# PROC099A_LP_Connector.net
KiCad netlist of a schematic drawn in Altium Designer
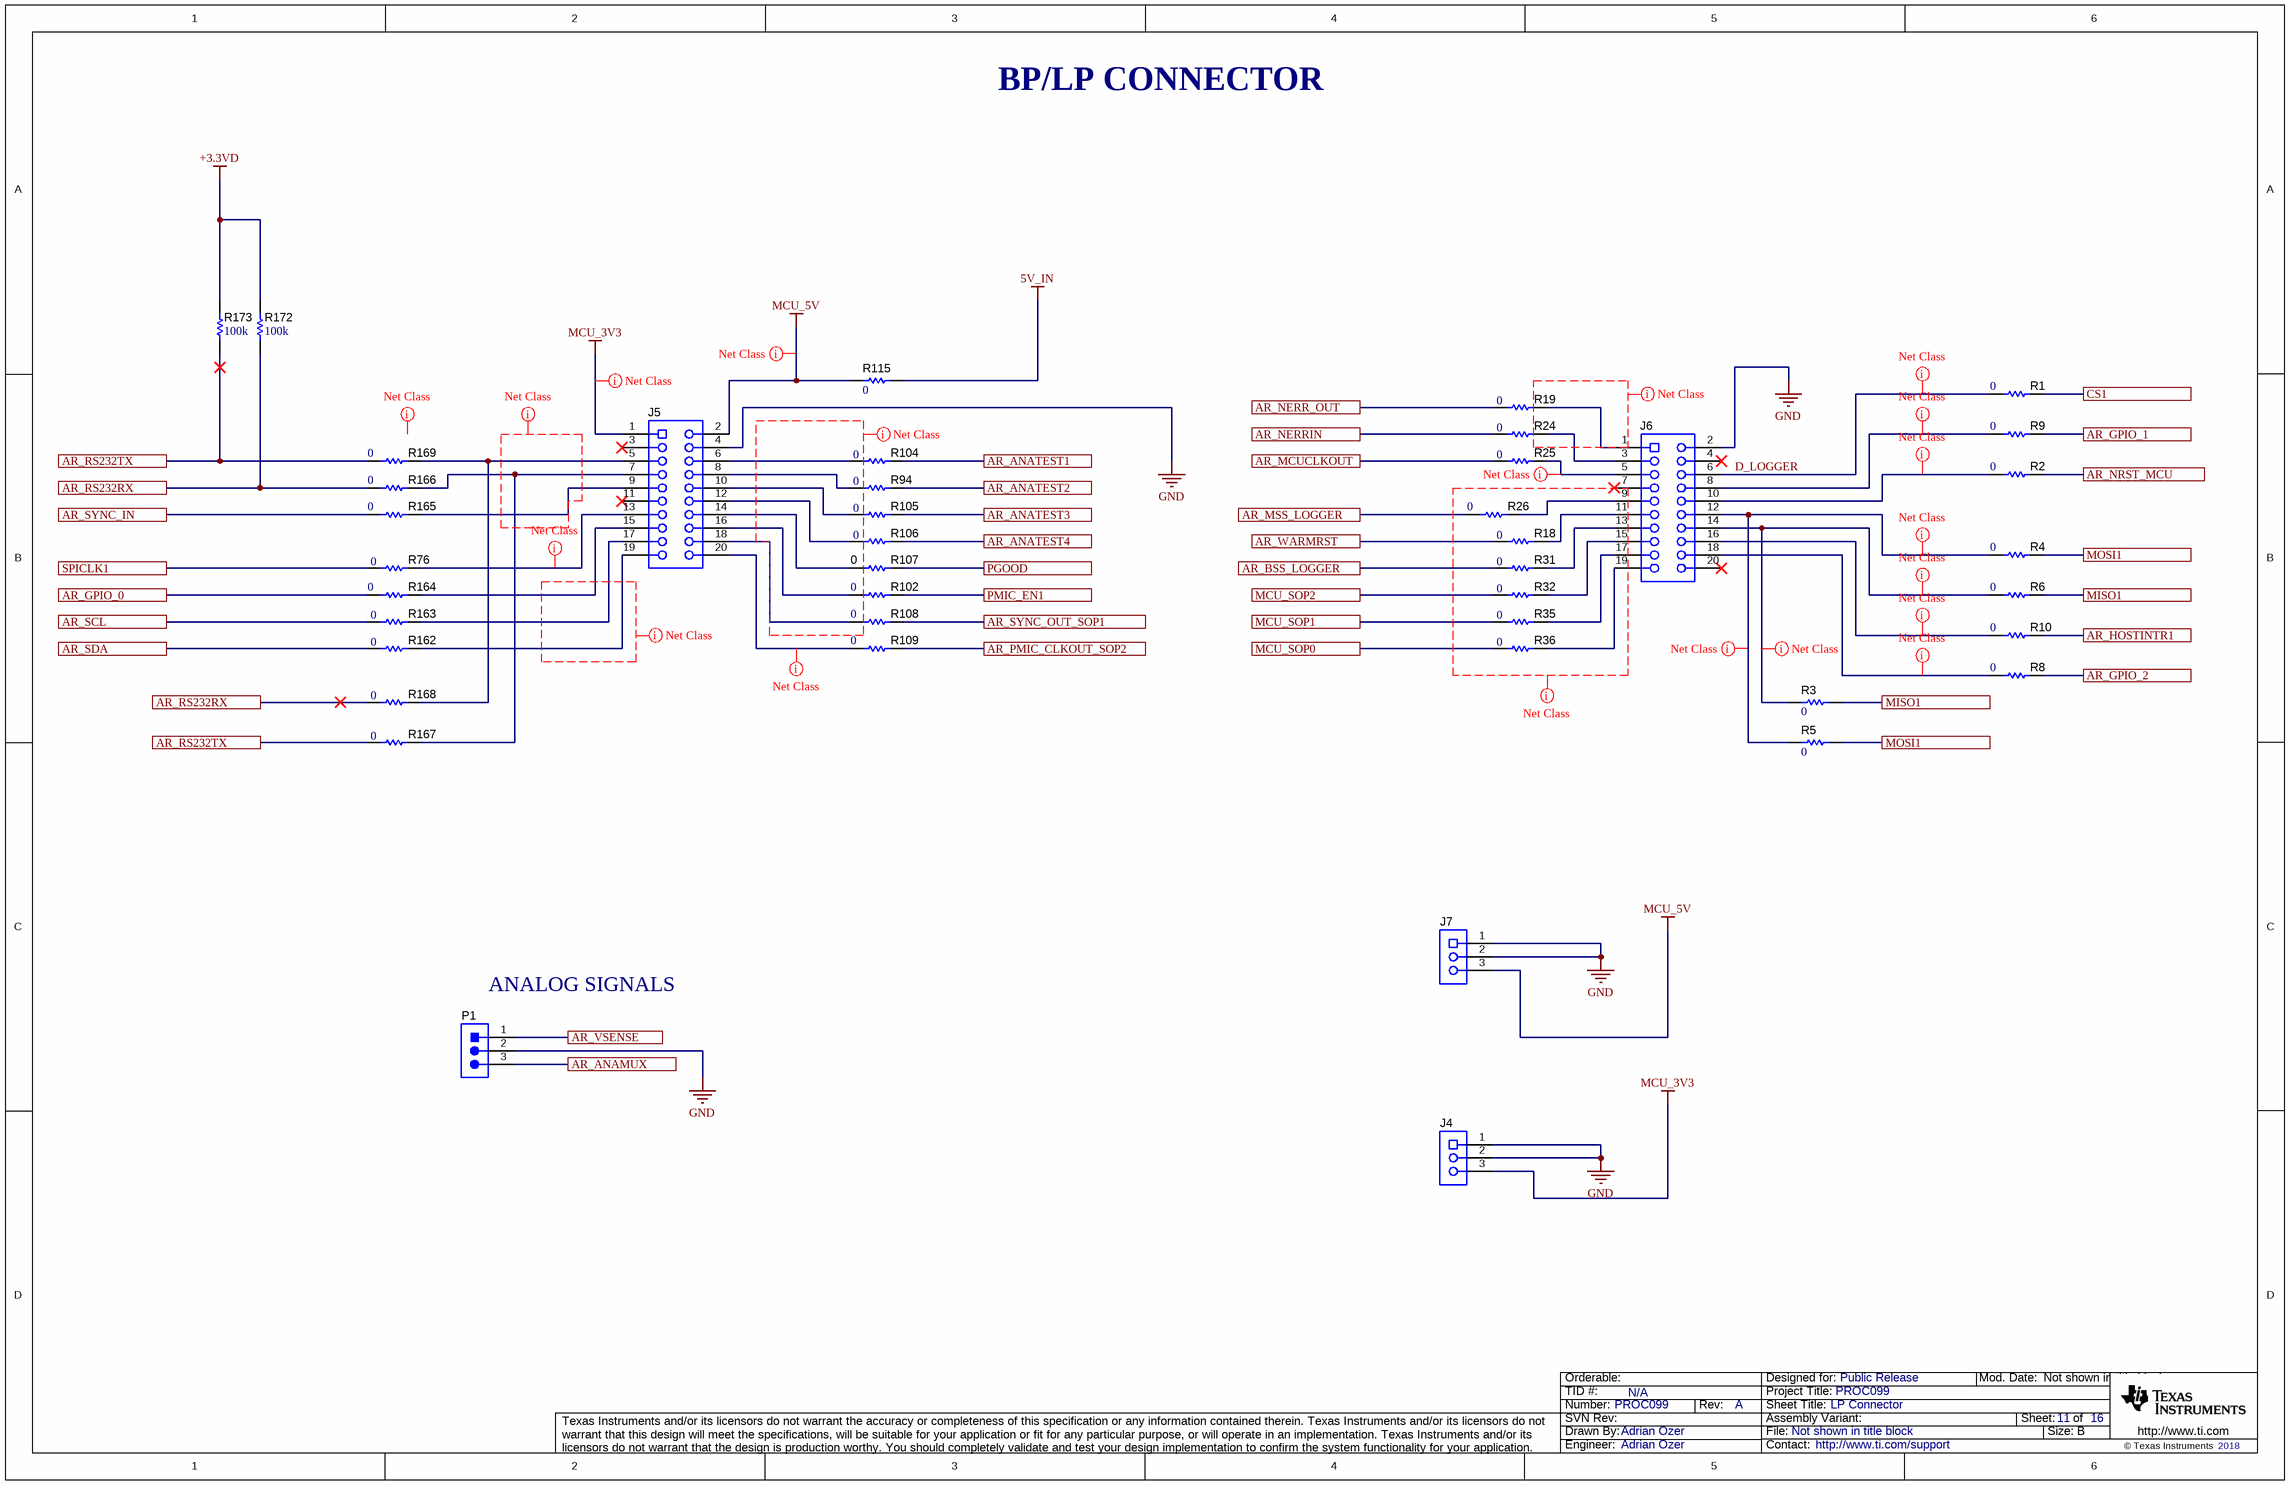
[diagram p0: PROC099A_LP Connector.SchDoc]

(export (version "E")
  (design (tool "Eeschema 10.0.6"))
  (components
    (comp (ref "J4")
      (value "SSM-103-S-SV")
      (footprint "Samtec_SSM-103-x-SV")
      (description "Receptacle, 2.54mm, 3x1, Gold with Tin tail, SMT")
      (fields (field (name "MANUFACTURER") "Samtec"))
      (libsource (lib "Altium Vault - TI") (part "CMP-0078183-1"))
    )
    (comp (ref "J5")
      (value "SSM-110-S-DV")
      (footprint "Samtec_SSM-110-x-DV")
      (description "Receptacle, 2.54mm, 10x2, Gold with Tin tail, SMT")
      (fields (field (name "MANUFACTURER") "Samtec"))
      (libsource (lib "Altium Vault - TI") (part "CMP-0078182-1"))
    )
    (comp (ref "J6")
      (value "SSM-110-S-DV")
      (footprint "Samtec_SSM-110-x-DV")
      (description "Receptacle, 2.54mm, 10x2, Gold with Tin tail, SMT")
      (fields (field (name "MANUFACTURER") "Samtec"))
      (libsource (lib "Altium Vault - TI") (part "CMP-0078182-1"))
    )
    (comp (ref "J7")
      (value "SSM-103-S-SV")
      (footprint "Samtec_SSM-103-x-SV")
      (description "Receptacle, 2.54mm, 3x1, Gold with Tin tail, SMT")
      (fields (field (name "MANUFACTURER") "Samtec"))
      (libsource (lib "Altium Vault - TI") (part "CMP-0078183-1"))
    )
    (comp (ref "P1")
      (value "TSW-103-07-T-S")
      (footprint "Samtec_TSW-103-07-T-S")
      (description "Header, 2.54 mm, 3x1, Tin, TH")
      (fields (field (name "MANUFACTURER") "Samtec"))
      (libsource (lib "Altium Vault - TI") (part "Header_3x1"))
    )
    (comp (ref "R1")
      (value "CRCW02010000Z0ED")
      (footprint "0201_Silk")
      (description "RES, 0, 5%, 0.05 W, 0201")
      (fields (field (name "MANUFACTURER") "Vishay-Dale") (field (name "VALUEDISPLAYED") "0"))
      (libsource (lib "Altium Vault - TI") (part "Resistor"))
    )
    (comp (ref "R2")
      (value "CRCW02010000Z0ED")
      (footprint "0201_Silk")
      (description "RES, 0, 5%, 0.05 W, 0201")
      (fields (field (name "MANUFACTURER") "Vishay-Dale") (field (name "VALUEDISPLAYED") "0"))
      (libsource (lib "Altium Vault - TI") (part "Resistor"))
    )
    (comp (ref "R3")
      (value "CRCW02010000Z0ED")
      (footprint "0201_Silk")
      (description "RES, 0, 5%, 0.05 W, 0201")
      (fields (field (name "MANUFACTURER") "Vishay-Dale") (field (name "VALUEDISPLAYED") "0"))
      (libsource (lib "Altium Vault - TI") (part "Resistor"))
    )
    (comp (ref "R4")
      (value "CRCW02010000Z0ED")
      (footprint "0201_Silk")
      (description "RES, 0, 5%, 0.05 W, 0201")
      (fields (field (name "MANUFACTURER") "Vishay-Dale") (field (name "VALUEDISPLAYED") "0"))
      (libsource (lib "Altium Vault - TI") (part "Resistor"))
    )
    (comp (ref "R5")
      (value "CRCW02010000Z0ED")
      (footprint "0201_Silk")
      (description "RES, 0, 5%, 0.05 W, 0201")
      (fields (field (name "MANUFACTURER") "Vishay-Dale") (field (name "VALUEDISPLAYED") "0"))
      (libsource (lib "Altium Vault - TI") (part "Resistor"))
    )
    (comp (ref "R6")
      (value "CRCW02010000Z0ED")
      (footprint "0201_Silk")
      (description "RES, 0, 5%, 0.05 W, 0201")
      (fields (field (name "MANUFACTURER") "Vishay-Dale") (field (name "VALUEDISPLAYED") "0"))
      (libsource (lib "Altium Vault - TI") (part "Resistor"))
    )
    (comp (ref "R8")
      (value "CRCW02010000Z0ED")
      (footprint "0201_Silk")
      (description "RES, 0, 5%, 0.05 W, 0201")
      (fields (field (name "MANUFACTURER") "Vishay-Dale") (field (name "VALUEDISPLAYED") "0"))
      (libsource (lib "Altium Vault - TI") (part "Resistor"))
    )
    (comp (ref "R9")
      (value "CRCW02010000Z0ED")
      (footprint "0201_Silk")
      (description "RES, 0, 5%, 0.05 W, 0201")
      (fields (field (name "MANUFACTURER") "Vishay-Dale") (field (name "VALUEDISPLAYED") "0"))
      (libsource (lib "Altium Vault - TI") (part "Resistor"))
    )
    (comp (ref "R10")
      (value "CRCW02010000Z0ED")
      (footprint "0201_Silk")
      (description "RES, 0, 5%, 0.05 W, 0201")
      (fields (field (name "MANUFACTURER") "Vishay-Dale") (field (name "VALUEDISPLAYED") "0"))
      (libsource (lib "Altium Vault - TI") (part "Resistor"))
    )
    (comp (ref "R18")
      (value "CRCW02010000Z0ED")
      (footprint "0201_Silk")
      (description "RES, 0, 5%, 0.05 W, 0201")
      (fields (field (name "MANUFACTURER") "Vishay-Dale") (field (name "VALUEDISPLAYED") "0"))
      (libsource (lib "Altium Vault - TI") (part "Resistor"))
    )
    (comp (ref "R19")
      (value "CRCW02010000Z0ED")
      (footprint "0201_Silk")
      (description "RES, 0, 5%, 0.05 W, 0201")
      (fields (field (name "MANUFACTURER") "Vishay-Dale") (field (name "VALUEDISPLAYED") "0"))
      (libsource (lib "Altium Vault - TI") (part "Resistor"))
    )
    (comp (ref "R24")
      (value "CRCW02010000Z0ED")
      (footprint "0201_Silk")
      (description "RES, 0, 5%, 0.05 W, 0201")
      (fields (field (name "MANUFACTURER") "Vishay-Dale") (field (name "VALUEDISPLAYED") "0"))
      (libsource (lib "Altium Vault - TI") (part "Resistor"))
    )
    (comp (ref "R25")
      (value "CRCW02010000Z0ED")
      (footprint "0201_Silk")
      (description "RES, 0, 5%, 0.05 W, 0201")
      (fields (field (name "MANUFACTURER") "Vishay-Dale") (field (name "VALUEDISPLAYED") "0"))
      (libsource (lib "Altium Vault - TI") (part "Resistor"))
    )
    (comp (ref "R26")
      (value "CRCW02010000Z0ED")
      (footprint "0201_Silk")
      (description "RES, 0, 5%, 0.05 W, 0201")
      (fields (field (name "MANUFACTURER") "Vishay-Dale") (field (name "VALUEDISPLAYED") "0"))
      (libsource (lib "Altium Vault - TI") (part "Resistor"))
    )
    (comp (ref "R31")
      (value "CRCW02010000Z0ED")
      (footprint "0201_Silk")
      (description "RES, 0, 5%, 0.05 W, 0201")
      (fields (field (name "MANUFACTURER") "Vishay-Dale") (field (name "VALUEDISPLAYED") "0"))
      (libsource (lib "Altium Vault - TI") (part "Resistor"))
    )
    (comp (ref "R32")
      (value "CRCW02010000Z0ED")
      (footprint "0201_Silk")
      (description "RES, 0, 5%, 0.05 W, 0201")
      (fields (field (name "MANUFACTURER") "Vishay-Dale") (field (name "VALUEDISPLAYED") "0"))
      (libsource (lib "Altium Vault - TI") (part "Resistor"))
    )
    (comp (ref "R35")
      (value "CRCW02010000Z0ED")
      (footprint "0201_Silk")
      (description "RES, 0, 5%, 0.05 W, 0201")
      (fields (field (name "MANUFACTURER") "Vishay-Dale") (field (name "VALUEDISPLAYED") "0"))
      (libsource (lib "Altium Vault - TI") (part "Resistor"))
    )
    (comp (ref "R36")
      (value "CRCW02010000Z0ED")
      (footprint "0201_Silk")
      (description "RES, 0, 5%, 0.05 W, 0201")
      (fields (field (name "MANUFACTURER") "Vishay-Dale") (field (name "VALUEDISPLAYED") "0"))
      (libsource (lib "Altium Vault - TI") (part "Resistor"))
    )
    (comp (ref "R76")
      (value "CRCW02010000Z0ED")
      (footprint "0201_Silk")
      (description "RES, 0, 5%, 0.05 W, 0201")
      (fields (field (name "MANUFACTURER") "Vishay-Dale") (field (name "VALUEDISPLAYED") "0"))
      (libsource (lib "Altium Vault - TI") (part "CMP-0027008-4"))
    )
    (comp (ref "R94")
      (value "CRCW02010000Z0ED")
      (footprint "0201_Silk")
      (description "RES, 0, 5%, 0.05 W, 0201")
      (fields (field (name "MANUFACTURER") "Vishay-Dale") (field (name "VALUEDISPLAYED") "0"))
      (libsource (lib "Altium Vault - TI") (part "Resistor"))
    )
    (comp (ref "R102")
      (value "CRCW02010000Z0ED")
      (footprint "0201_Silk")
      (description "RES, 0, 5%, 0.05 W, 0201")
      (fields (field (name "MANUFACTURER") "Vishay-Dale") (field (name "VALUEDISPLAYED") "0"))
      (libsource (lib "Altium Vault - TI") (part "Resistor"))
    )
    (comp (ref "R104")
      (value "CRCW02010000Z0ED")
      (footprint "0201_Silk")
      (description "RES, 0, 5%, 0.05 W, 0201")
      (fields (field (name "MANUFACTURER") "Vishay-Dale") (field (name "VALUEDISPLAYED") "0"))
      (libsource (lib "Altium Vault - TI") (part "CMP-0027008-4"))
    )
    (comp (ref "R105")
      (value "CRCW02010000Z0ED")
      (footprint "0201_Silk")
      (description "RES, 0, 5%, 0.05 W, 0201")
      (fields (field (name "MANUFACTURER") "Vishay-Dale") (field (name "VALUEDISPLAYED") "0"))
      (libsource (lib "Altium Vault - TI") (part "Resistor"))
    )
    (comp (ref "R106")
      (value "CRCW02010000Z0ED")
      (footprint "0201_Silk")
      (description "RES, 0, 5%, 0.05 W, 0201")
      (fields (field (name "MANUFACTURER") "Vishay-Dale") (field (name "VALUEDISPLAYED") "0"))
      (libsource (lib "Altium Vault - TI") (part "Resistor"))
    )
    (comp (ref "R107")
      (value "ERJ-2GE0R00X")
      (footprint "0402L")
      (description "RES, 0, 5%, 0.063 W, 0402")
      (fields
        (field (name "MANUFACTURER") "Panasonic")
        (field (name "VALUEDISPLAYED") "0")
        (field (name "PUBLISHER") "Texas Instruments")
      )
      (libsource (lib "Altium Vault - TI") (part "Resistor"))
    )
    (comp (ref "R108")
      (value "CRCW02010000Z0ED")
      (footprint "0201_Silk")
      (description "RES, 0, 5%, 0.05 W, 0201")
      (fields (field (name "MANUFACTURER") "Vishay-Dale") (field (name "VALUEDISPLAYED") "0"))
      (libsource (lib "Altium Vault - TI") (part "Resistor"))
    )
    (comp (ref "R109")
      (value "CRCW02010000Z0ED")
      (footprint "0201_Silk")
      (description "RES, 0, 5%, 0.05 W, 0201")
      (fields (field (name "MANUFACTURER") "Vishay-Dale") (field (name "VALUEDISPLAYED") "0"))
      (libsource (lib "Altium Vault - TI") (part "Resistor"))
    )
    (comp (ref "R115")
      (value "CRCW20100000Z0EF")
      (footprint "2010")
      (description "RES, 0, 5%, 0.75 W, AEC-Q200 Grade 0, 2010")
      (fields (field (name "MANUFACTURER") "Vishay-Dale") (field (name "VALUEDISPLAYED") "0"))
      (libsource (lib "Altium Vault - TI") (part "Resistor"))
    )
    (comp (ref "R162")
      (value "CRCW02010000Z0ED")
      (footprint "0201_Silk")
      (description "RES, 0, 5%, 0.05 W, 0201")
      (fields (field (name "MANUFACTURER") "Vishay-Dale") (field (name "VALUEDISPLAYED") "0"))
      (libsource (lib "Altium Vault - TI") (part "Resistor"))
    )
    (comp (ref "R163")
      (value "CRCW02010000Z0ED")
      (footprint "0201_Silk")
      (description "RES, 0, 5%, 0.05 W, 0201")
      (fields (field (name "MANUFACTURER") "Vishay-Dale") (field (name "VALUEDISPLAYED") "0"))
      (libsource (lib "Altium Vault - TI") (part "Resistor"))
    )
    (comp (ref "R164")
      (value "CRCW02010000Z0ED")
      (footprint "0201_Silk")
      (description "RES, 0, 5%, 0.05 W, 0201")
      (fields (field (name "MANUFACTURER") "Vishay-Dale") (field (name "VALUEDISPLAYED") "0"))
      (libsource (lib "Altium Vault - TI") (part "Resistor"))
    )
    (comp (ref "R165")
      (value "CRCW02010000Z0ED")
      (footprint "0201_Silk")
      (description "RES, 0, 5%, 0.05 W, 0201")
      (fields (field (name "MANUFACTURER") "Vishay-Dale") (field (name "VALUEDISPLAYED") "0"))
      (libsource (lib "Altium Vault - TI") (part "Resistor"))
    )
    (comp (ref "R166")
      (value "CRCW02010000Z0ED")
      (footprint "0201_Silk")
      (description "RES, 0, 5%, 0.05 W, 0201")
      (fields (field (name "MANUFACTURER") "Vishay-Dale") (field (name "VALUEDISPLAYED") "0"))
      (libsource (lib "Altium Vault - TI") (part "Resistor"))
    )
    (comp (ref "R167")
      (value "CRCW02010000Z0ED")
      (footprint "0201_Silk")
      (description "RES, 0, 5%, 0.05 W, 0201")
      (fields (field (name "MANUFACTURER") "Vishay-Dale") (field (name "VALUEDISPLAYED") "0"))
      (libsource (lib "Altium Vault - TI") (part "Resistor"))
    )
    (comp (ref "R168")
      (value "CRCW02010000Z0ED")
      (footprint "0201_Silk")
      (description "RES, 0, 5%, 0.05 W, 0201")
      (fields (field (name "MANUFACTURER") "Vishay-Dale") (field (name "VALUEDISPLAYED") "0"))
      (libsource (lib "Altium Vault - TI") (part "Resistor"))
    )
    (comp (ref "R169")
      (value "CRCW02010000Z0ED")
      (footprint "0201_Silk")
      (description "RES, 0, 5%, 0.05 W, 0201")
      (fields (field (name "MANUFACTURER") "Vishay-Dale") (field (name "VALUEDISPLAYED") "0"))
      (libsource (lib "Altium Vault - TI") (part "Resistor"))
    )
    (comp (ref "R172")
      (value "CRCW0402100KFKED")
      (footprint "0402L")
      (description "RES, 100 k, 1%, 0.063 W, AEC-Q200 Grade 0, 0402")
      (fields (field (name "MANUFACTURER") "Vishay-Dale") (field (name "VALUEDISPLAYED") "100k"))
      (libsource (lib "Altium Vault - TI") (part "Resistor"))
    )
    (comp (ref "R173")
      (value "CRCW0402100KFKED")
      (footprint "0402L")
      (description "RES, 100 k, 1%, 0.063 W, AEC-Q200 Grade 0, 0402")
      (fields (field (name "MANUFACTURER") "Vishay-Dale") (field (name "VALUEDISPLAYED") "100k"))
      (libsource (lib "Altium Vault - TI") (part "Resistor"))
    )
  )
  (nets
    (net (code "1") (name "+3.3VD") (class "Default")
      (node (ref "R172") (pin "2") (pinfunction "2_2") (pintype "passive"))
      (node (ref "R173") (pin "2") (pinfunction "2_2") (pintype "passive"))
    )
    (net (code "2") (name "/AR_ANAMUX") (class "Default")
      (node (ref "P1") (pin "3") (pinfunction "3_3") (pintype "passive"))
    )
    (net (code "3") (name "/AR_ANATEST1") (class "Default")
      (node (ref "R104") (pin "2") (pinfunction "2_2") (pintype "passive"))
    )
    (net (code "4") (name "/AR_ANATEST2") (class "Default")
      (node (ref "R94") (pin "2") (pinfunction "2_2") (pintype "passive"))
    )
    (net (code "5") (name "/AR_ANATEST3") (class "Default")
      (node (ref "R105") (pin "2") (pinfunction "2_2") (pintype "passive"))
    )
    (net (code "6") (name "/AR_ANATEST4") (class "Default")
      (node (ref "R106") (pin "2") (pinfunction "2_2") (pintype "passive"))
    )
    (net (code "7") (name "/AR_BSS_LOGGER") (class "Default")
      (node (ref "R31") (pin "1") (pinfunction "1_1") (pintype "passive"))
    )
    (net (code "8") (name "/AR_GPIO_0") (class "Default")
      (node (ref "R164") (pin "1") (pinfunction "1_1") (pintype "passive"))
    )
    (net (code "9") (name "/AR_GPIO_1") (class "Default")
      (node (ref "R9") (pin "2") (pinfunction "2_2") (pintype "passive"))
    )
    (net (code "10") (name "/AR_GPIO_2") (class "Default")
      (node (ref "R8") (pin "2") (pinfunction "2_2") (pintype "passive"))
    )
    (net (code "11") (name "/AR_HOSTINTR1") (class "Default")
      (node (ref "R10") (pin "2") (pinfunction "2_2") (pintype "passive"))
    )
    (net (code "12") (name "/AR_MCUCLKOUT") (class "Default")
      (node (ref "R25") (pin "1") (pinfunction "1_1") (pintype "passive"))
    )
    (net (code "13") (name "/AR_MSS_LOGGER") (class "Default")
      (node (ref "R26") (pin "1") (pinfunction "1_1") (pintype "passive"))
    )
    (net (code "14") (name "/AR_NERRIN") (class "Default")
      (node (ref "R24") (pin "1") (pinfunction "1_1") (pintype "passive"))
    )
    (net (code "15") (name "/AR_NERR_OUT") (class "Default")
      (node (ref "R19") (pin "1") (pinfunction "1_1") (pintype "passive"))
    )
    (net (code "16") (name "/AR_NRST_MCU") (class "Default")
      (node (ref "R2") (pin "2") (pinfunction "2_2") (pintype "passive"))
    )
    (net (code "17") (name "/AR_PMIC_CLKOUT_SOP2") (class "Default")
      (node (ref "R109") (pin "2") (pinfunction "2_2") (pintype "passive"))
    )
    (net (code "18") (name "/AR_RS232RX") (class "Default")
      (node (ref "R166") (pin "1") (pinfunction "1_1") (pintype "passive"))
      (node (ref "R168") (pin "1") (pinfunction "1_1") (pintype "passive"))
      (node (ref "R172") (pin "1") (pinfunction "1_1") (pintype "passive"))
    )
    (net (code "19") (name "/AR_RS232TX") (class "Default")
      (node (ref "R167") (pin "1") (pinfunction "1_1") (pintype "passive"))
      (node (ref "R169") (pin "1") (pinfunction "1_1") (pintype "passive"))
      (node (ref "R173") (pin "1") (pinfunction "1_1") (pintype "passive"))
    )
    (net (code "20") (name "/AR_SCL") (class "Default")
      (node (ref "R163") (pin "1") (pinfunction "1_1") (pintype "passive"))
    )
    (net (code "21") (name "/AR_SDA") (class "Default")
      (node (ref "R162") (pin "1") (pinfunction "1_1") (pintype "passive"))
    )
    (net (code "22") (name "/AR_SYNC_IN") (class "Default")
      (node (ref "R165") (pin "1") (pinfunction "1_1") (pintype "passive"))
    )
    (net (code "23") (name "/AR_SYNC_OUT_SOP1") (class "Default")
      (node (ref "R108") (pin "2") (pinfunction "2_2") (pintype "passive"))
    )
    (net (code "24") (name "/AR_VSENSE") (class "Default")
      (node (ref "P1") (pin "1") (pinfunction "1_1") (pintype "passive"))
    )
    (net (code "25") (name "/AR_WARMRST") (class "Default")
      (node (ref "R18") (pin "1") (pinfunction "1_1") (pintype "passive"))
    )
    (net (code "26") (name "/CS1") (class "Default")
      (node (ref "R1") (pin "2") (pinfunction "2_2") (pintype "passive"))
    )
    (net (code "27") (name "/D_LOGGER") (class "Default")
      (node (ref "J6") (pin "6") (pinfunction "6_6") (pintype "passive"))
      (node (ref "R1") (pin "1") (pinfunction "1_1") (pintype "passive"))
    )
    (net (code "28") (name "/MCU_SOP0") (class "Default")
      (node (ref "R36") (pin "1") (pinfunction "1_1") (pintype "passive"))
    )
    (net (code "29") (name "/MCU_SOP1") (class "Default")
      (node (ref "R35") (pin "1") (pinfunction "1_1") (pintype "passive"))
    )
    (net (code "30") (name "/MCU_SOP2") (class "Default")
      (node (ref "R32") (pin "1") (pinfunction "1_1") (pintype "passive"))
    )
    (net (code "31") (name "/MISO1") (class "Default")
      (node (ref "R3") (pin "2") (pinfunction "2_2") (pintype "passive"))
      (node (ref "R6") (pin "2") (pinfunction "2_2") (pintype "passive"))
    )
    (net (code "32") (name "/MOSI1") (class "Default")
      (node (ref "R4") (pin "2") (pinfunction "2_2") (pintype "passive"))
      (node (ref "R5") (pin "2") (pinfunction "2_2") (pintype "passive"))
    )
    (net (code "33") (name "/PGOOD") (class "Default")
      (node (ref "R107") (pin "2") (pinfunction "2_2") (pintype "passive"))
    )
    (net (code "34") (name "/PMIC_EN1") (class "Default")
      (node (ref "R102") (pin "2") (pinfunction "2_2") (pintype "passive"))
    )
    (net (code "35") (name "/SPICLK1") (class "Default")
      (node (ref "R76") (pin "1") (pinfunction "1_1") (pintype "passive"))
    )
    (net (code "36") (name "5V_IN") (class "Default")
      (node (ref "R115") (pin "2") (pinfunction "2_2") (pintype "passive"))
    )
    (net (code "37") (name "GND") (class "Default")
      (node (ref "J4") (pin "1") (pinfunction "1_1") (pintype "passive"))
      (node (ref "J4") (pin "2") (pinfunction "2_2") (pintype "passive"))
      (node (ref "J5") (pin "4") (pinfunction "4_4") (pintype "passive"))
      (node (ref "J6") (pin "2") (pinfunction "2_2") (pintype "passive"))
      (node (ref "J7") (pin "1") (pinfunction "1_1") (pintype "passive"))
      (node (ref "J7") (pin "2") (pinfunction "2_2") (pintype "passive"))
      (node (ref "P1") (pin "2") (pinfunction "2_2") (pintype "passive"))
    )
    (net (code "38") (name "MCU_3V3") (class "Default")
      (node (ref "J4") (pin "3") (pinfunction "3_3") (pintype "passive"))
      (node (ref "J5") (pin "1") (pinfunction "1_1") (pintype "passive"))
    )
    (net (code "39") (name "MCU_5V") (class "Default")
      (node (ref "J5") (pin "2") (pinfunction "2_2") (pintype "passive"))
      (node (ref "J7") (pin "3") (pinfunction "3_3") (pintype "passive"))
      (node (ref "R115") (pin "1") (pinfunction "1_1") (pintype "passive"))
    )
    (net (code "40") (name "Net-(J5-Pad5)") (class "Default")
      (node (ref "J5") (pin "5") (pinfunction "5_5") (pintype "passive"))
      (node (ref "R168") (pin "2") (pinfunction "2_2") (pintype "passive"))
      (node (ref "R169") (pin "2") (pinfunction "2_2") (pintype "passive"))
    )
    (net (code "41") (name "Net-(J5-Pad6)") (class "Default")
      (node (ref "J5") (pin "6") (pinfunction "6_6") (pintype "passive"))
      (node (ref "R104") (pin "1") (pinfunction "1_1") (pintype "passive"))
    )
    (net (code "42") (name "Net-(J5-Pad7)") (class "Default")
      (node (ref "J5") (pin "7") (pinfunction "7_7") (pintype "passive"))
      (node (ref "R166") (pin "2") (pinfunction "2_2") (pintype "passive"))
      (node (ref "R167") (pin "2") (pinfunction "2_2") (pintype "passive"))
    )
    (net (code "43") (name "Net-(J5-Pad8)") (class "Default")
      (node (ref "J5") (pin "8") (pinfunction "8_8") (pintype "passive"))
      (node (ref "R94") (pin "1") (pinfunction "1_1") (pintype "passive"))
    )
    (net (code "44") (name "Net-(J5-Pad9)") (class "Default")
      (node (ref "J5") (pin "9") (pinfunction "9_9") (pintype "passive"))
      (node (ref "R165") (pin "2") (pinfunction "2_2") (pintype "passive"))
    )
    (net (code "45") (name "Net-(J5-Pad10)") (class "Default")
      (node (ref "J5") (pin "10") (pinfunction "10_10") (pintype "passive"))
      (node (ref "R105") (pin "1") (pinfunction "1_1") (pintype "passive"))
    )
    (net (code "46") (name "Net-(J5-Pad12)") (class "Default")
      (node (ref "J5") (pin "12") (pinfunction "12_12") (pintype "passive"))
      (node (ref "R106") (pin "1") (pinfunction "1_1") (pintype "passive"))
    )
    (net (code "47") (name "Net-(J5-Pad13)") (class "Default")
      (node (ref "J5") (pin "13") (pinfunction "13_13") (pintype "passive"))
      (node (ref "R76") (pin "2") (pinfunction "2_2") (pintype "passive"))
    )
    (net (code "48") (name "Net-(J5-Pad14)") (class "Default")
      (node (ref "J5") (pin "14") (pinfunction "14_14") (pintype "passive"))
      (node (ref "R107") (pin "1") (pinfunction "1_1") (pintype "passive"))
    )
    (net (code "49") (name "Net-(J5-Pad15)") (class "Default")
      (node (ref "J5") (pin "15") (pinfunction "15_15") (pintype "passive"))
      (node (ref "R164") (pin "2") (pinfunction "2_2") (pintype "passive"))
    )
    (net (code "50") (name "Net-(J5-Pad16)") (class "Default")
      (node (ref "J5") (pin "16") (pinfunction "16_16") (pintype "passive"))
      (node (ref "R102") (pin "1") (pinfunction "1_1") (pintype "passive"))
    )
    (net (code "51") (name "Net-(J5-Pad17)") (class "Default")
      (node (ref "J5") (pin "17") (pinfunction "17_17") (pintype "passive"))
      (node (ref "R163") (pin "2") (pinfunction "2_2") (pintype "passive"))
    )
    (net (code "52") (name "Net-(J5-Pad18)") (class "Default")
      (node (ref "J5") (pin "18") (pinfunction "18_18") (pintype "passive"))
      (node (ref "R108") (pin "1") (pinfunction "1_1") (pintype "passive"))
    )
    (net (code "53") (name "Net-(J5-Pad19)") (class "Default")
      (node (ref "J5") (pin "19") (pinfunction "19_19") (pintype "passive"))
      (node (ref "R162") (pin "2") (pinfunction "2_2") (pintype "passive"))
    )
    (net (code "54") (name "Net-(J5-Pad20)") (class "Default")
      (node (ref "J5") (pin "20") (pinfunction "20_20") (pintype "passive"))
      (node (ref "R109") (pin "1") (pinfunction "1_1") (pintype "passive"))
    )
    (net (code "55") (name "Net-(J6-Pad1)") (class "Default")
      (node (ref "J6") (pin "1") (pinfunction "1_1") (pintype "passive"))
      (node (ref "R19") (pin "2") (pinfunction "2_2") (pintype "passive"))
    )
    (net (code "56") (name "Net-(J6-Pad3)") (class "Default")
      (node (ref "J6") (pin "3") (pinfunction "3_3") (pintype "passive"))
      (node (ref "R24") (pin "2") (pinfunction "2_2") (pintype "passive"))
    )
    (net (code "57") (name "Net-(J6-Pad5)") (class "Default")
      (node (ref "J6") (pin "5") (pinfunction "5_5") (pintype "passive"))
      (node (ref "R25") (pin "2") (pinfunction "2_2") (pintype "passive"))
    )
    (net (code "58") (name "Net-(J6-Pad8)") (class "Default")
      (node (ref "J6") (pin "8") (pinfunction "8_8") (pintype "passive"))
      (node (ref "R9") (pin "1") (pinfunction "1_1") (pintype "passive"))
    )
    (net (code "59") (name "Net-(J6-Pad9)") (class "Default")
      (node (ref "J6") (pin "9") (pinfunction "9_9") (pintype "passive"))
      (node (ref "R26") (pin "2") (pinfunction "2_2") (pintype "passive"))
    )
    (net (code "60") (name "Net-(J6-Pad10)") (class "Default")
      (node (ref "J6") (pin "10") (pinfunction "10_10") (pintype "passive"))
      (node (ref "R2") (pin "1") (pinfunction "1_1") (pintype "passive"))
    )
    (net (code "61") (name "Net-(J6-Pad11)") (class "Default")
      (node (ref "J6") (pin "11") (pinfunction "11_11") (pintype "passive"))
      (node (ref "R18") (pin "2") (pinfunction "2_2") (pintype "passive"))
    )
    (net (code "62") (name "Net-(J6-Pad12)") (class "Default")
      (node (ref "J6") (pin "12") (pinfunction "12_12") (pintype "passive"))
      (node (ref "R4") (pin "1") (pinfunction "1_1") (pintype "passive"))
      (node (ref "R5") (pin "1") (pinfunction "1_1") (pintype "passive"))
    )
    (net (code "63") (name "Net-(J6-Pad13)") (class "Default")
      (node (ref "J6") (pin "13") (pinfunction "13_13") (pintype "passive"))
      (node (ref "R31") (pin "2") (pinfunction "2_2") (pintype "passive"))
    )
    (net (code "64") (name "Net-(J6-Pad14)") (class "Default")
      (node (ref "J6") (pin "14") (pinfunction "14_14") (pintype "passive"))
      (node (ref "R3") (pin "1") (pinfunction "1_1") (pintype "passive"))
      (node (ref "R6") (pin "1") (pinfunction "1_1") (pintype "passive"))
    )
    (net (code "65") (name "Net-(J6-Pad15)") (class "Default")
      (node (ref "J6") (pin "15") (pinfunction "15_15") (pintype "passive"))
      (node (ref "R32") (pin "2") (pinfunction "2_2") (pintype "passive"))
    )
    (net (code "66") (name "Net-(J6-Pad16)") (class "Default")
      (node (ref "J6") (pin "16") (pinfunction "16_16") (pintype "passive"))
      (node (ref "R10") (pin "1") (pinfunction "1_1") (pintype "passive"))
    )
    (net (code "67") (name "Net-(J6-Pad17)") (class "Default")
      (node (ref "J6") (pin "17") (pinfunction "17_17") (pintype "passive"))
      (node (ref "R35") (pin "2") (pinfunction "2_2") (pintype "passive"))
    )
    (net (code "68") (name "Net-(J6-Pad18)") (class "Default")
      (node (ref "J6") (pin "18") (pinfunction "18_18") (pintype "passive"))
      (node (ref "R8") (pin "1") (pinfunction "1_1") (pintype "passive"))
    )
    (net (code "69") (name "Net-(J6-Pad19)") (class "Default")
      (node (ref "J6") (pin "19") (pinfunction "19_19") (pintype "passive"))
      (node (ref "R36") (pin "2") (pinfunction "2_2") (pintype "passive"))
    )
    (net (code "70") (name "unconnected-(J5-Pad3)") (class "Default")
      (node (ref "J5") (pin "3") (pinfunction "3_3") (pintype "passive+no_connect"))
    )
    (net (code "71") (name "unconnected-(J5-Pad11)") (class "Default")
      (node (ref "J5") (pin "11") (pinfunction "11_11") (pintype "passive+no_connect"))
    )
    (net (code "72") (name "unconnected-(J6-Pad4)") (class "Default")
      (node (ref "J6") (pin "4") (pinfunction "4_4") (pintype "passive+no_connect"))
    )
    (net (code "73") (name "unconnected-(J6-Pad7)") (class "Default")
      (node (ref "J6") (pin "7") (pinfunction "7_7") (pintype "passive+no_connect"))
    )
    (net (code "74") (name "unconnected-(J6-Pad20)") (class "Default")
      (node (ref "J6") (pin "20") (pinfunction "20_20") (pintype "passive+no_connect"))
    )
  )
)
